# Amplifier_Breakout.net
KiCad netlist of a schematic drawn in EAGLE
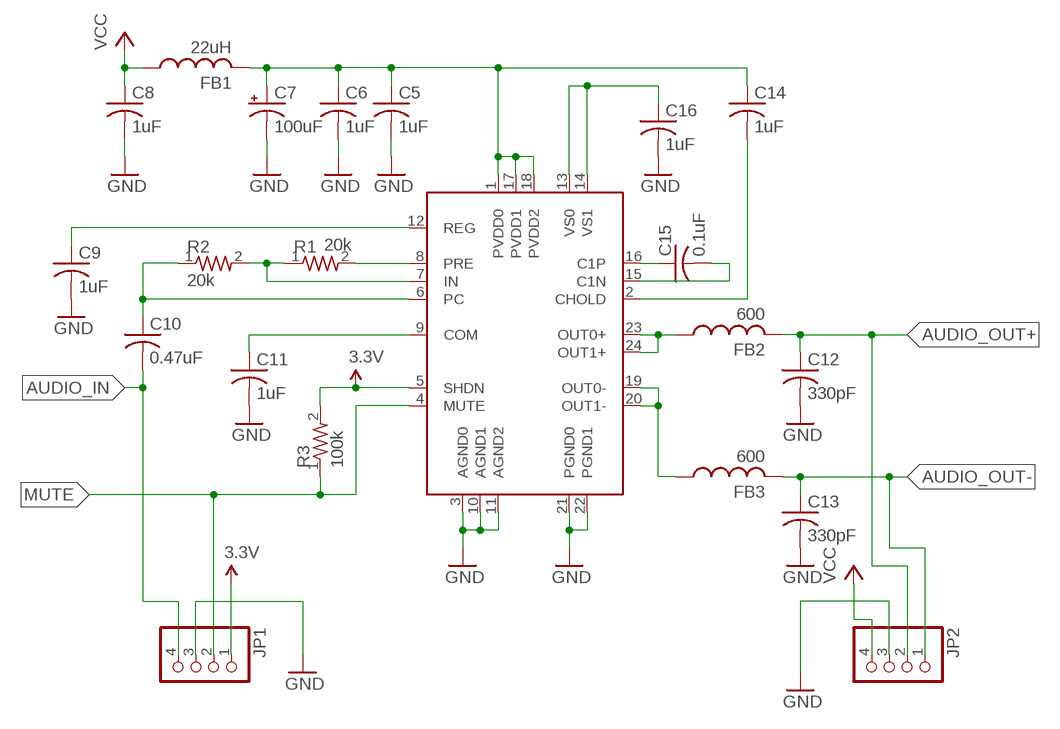
[diagram p0: schematic, sheet 1]

(export (version "E")
  (design (tool "Eeschema 10.0.6"))
  (components
    (comp (ref "C5")
      (value "1uF")
      (footprint "eagle-import:FB-0805")
      (libsource (lib "eagle-import") (part "0805_CAP"))
    )
    (comp (ref "C6")
      (value "1uF")
      (footprint "eagle-import:FB-0805")
      (libsource (lib "eagle-import") (part "0805_CAP"))
    )
    (comp (ref "C7")
      (value "100uF")
      (footprint "eagle-import:CAP_F")
      (libsource (lib "eagle-import") (part "CAP_POL_F"))
    )
    (comp (ref "C8")
      (value "1uF")
      (footprint "eagle-import:FB-0805")
      (libsource (lib "eagle-import") (part "0805_CAP"))
    )
    (comp (ref "C9")
      (value "1uF")
      (footprint "eagle-import:0603_RESISTOR")
      (libsource (lib "eagle-import") (part "0603_CAP"))
    )
    (comp (ref "C10")
      (value "0.47uF")
      (footprint "eagle-import:0603_RESISTOR")
      (libsource (lib "eagle-import") (part "0603_CAP"))
    )
    (comp (ref "C11")
      (value "1uF")
      (footprint "eagle-import:0603_RESISTOR")
      (libsource (lib "eagle-import") (part "0603_CAP"))
    )
    (comp (ref "C12")
      (value "330pF")
      (footprint "eagle-import:0603_RESISTOR")
      (libsource (lib "eagle-import") (part "0603_CAP"))
    )
    (comp (ref "C13")
      (value "330pF")
      (footprint "eagle-import:0603_RESISTOR")
      (libsource (lib "eagle-import") (part "0603_CAP"))
    )
    (comp (ref "C14")
      (value "1uF")
      (footprint "eagle-import:FB-0805")
      (libsource (lib "eagle-import") (part "0805_CAP"))
    )
    (comp (ref "C15")
      (value "0.1uF")
      (footprint "eagle-import:0603_RESISTOR")
      (libsource (lib "eagle-import") (part "0603_CAP"))
    )
    (comp (ref "C16")
      (value "1uF")
      (footprint "eagle-import:0603_RESISTOR")
      (libsource (lib "eagle-import") (part "0603_CAP"))
    )
    (comp (ref "FB1")
      (value "22uH")
      (footprint "eagle-import:FB-0805")
      (libsource (lib "eagle-import") (part "FB"))
    )
    (comp (ref "FB2")
      (value "600")
      (footprint "eagle-import:FB-0805")
      (libsource (lib "eagle-import") (part "FB"))
    )
    (comp (ref "FB3")
      (value "600")
      (footprint "eagle-import:FB-0805")
      (libsource (lib "eagle-import") (part "FB"))
    )
    (comp (ref "JP1")
      (value "PINHD-1X4")
      (footprint "eagle-import:1X04")
      (libsource (lib "eagle-import") (part "PINHD-1X4"))
    )
    (comp (ref "JP2")
      (value "PINHD-1X4")
      (footprint "eagle-import:1X04")
      (libsource (lib "eagle-import") (part "PINHD-1X4"))
    )
    (comp (ref "MAX1")
      (value "MAX9737")
      (footprint "eagle-import:TQFN24")
      (libsource (lib "eagle-import") (part "MAX9737"))
    )
    (comp (ref "R1")
      (value "20k")
      (footprint "eagle-import:0603_RESISTOR")
      (libsource (lib "eagle-import") (part "0603_RESISTOR"))
    )
    (comp (ref "R2")
      (value "20k")
      (footprint "eagle-import:0603_RESISTOR")
      (libsource (lib "eagle-import") (part "0603_RESISTOR"))
    )
    (comp (ref "R3")
      (value "100k")
      (footprint "eagle-import:0603_RESISTOR")
      (libsource (lib "eagle-import") (part "0603_RESISTOR"))
    )
  )
  (nets
    (net (code "1") (name "3.3V") (class "Default")
      (node (ref "JP1") (pin "1") (pinfunction "1_1") (pintype "passive"))
      (node (ref "MAX1") (pin "5") (pinfunction "SHDN_5") (pintype "input"))
      (node (ref "R3") (pin "2") (pinfunction "2_2") (pintype "passive"))
    )
    (net (code "2") (name "AUDIO_IN") (class "Default")
      (node (ref "C10") (pin "2") (pinfunction "2_2") (pintype "passive"))
      (node (ref "JP1") (pin "4") (pinfunction "4_4") (pintype "passive"))
    )
    (net (code "3") (name "AUDIO_OUT+") (class "Default")
      (node (ref "C12") (pin "1") (pinfunction "1_1") (pintype "passive"))
      (node (ref "FB2") (pin "2") (pinfunction "2_2") (pintype "passive"))
      (node (ref "JP2") (pin "2") (pinfunction "2_2") (pintype "passive"))
    )
    (net (code "4") (name "AUDIO_OUT-") (class "Default")
      (node (ref "C13") (pin "1") (pinfunction "1_1") (pintype "passive"))
      (node (ref "FB3") (pin "2") (pinfunction "2_2") (pintype "passive"))
      (node (ref "JP2") (pin "1") (pinfunction "1_1") (pintype "passive"))
    )
    (net (code "5") (name "GND") (class "Default")
      (node (ref "C11") (pin "2") (pinfunction "2_2") (pintype "passive"))
      (node (ref "C12") (pin "2") (pinfunction "2_2") (pintype "passive"))
      (node (ref "C13") (pin "2") (pinfunction "2_2") (pintype "passive"))
      (node (ref "C16") (pin "2") (pinfunction "2_2") (pintype "passive"))
      (node (ref "C5") (pin "2") (pinfunction "2_2") (pintype "passive"))
      (node (ref "C6") (pin "2") (pinfunction "2_2") (pintype "passive"))
      (node (ref "C7") (pin "-") (pinfunction "-_-") (pintype "passive"))
      (node (ref "C8") (pin "2") (pinfunction "2_2") (pintype "passive"))
      (node (ref "C9") (pin "2") (pinfunction "2_2") (pintype "passive"))
      (node (ref "JP1") (pin "3") (pinfunction "3_3") (pintype "passive"))
      (node (ref "JP2") (pin "3") (pinfunction "3_3") (pintype "passive"))
      (node (ref "MAX1") (pin "10") (pinfunction "AGND1_10") (pintype "power_in"))
      (node (ref "MAX1") (pin "11") (pinfunction "AGND2_11") (pintype "power_in"))
      (node (ref "MAX1") (pin "21") (pinfunction "PGND0_21") (pintype "power_in"))
      (node (ref "MAX1") (pin "22") (pinfunction "PGND1_22") (pintype "power_in"))
      (node (ref "MAX1") (pin "3") (pinfunction "AGND0_3") (pintype "power_in"))
    )
    (net (code "6") (name "MUTE") (class "Default")
      (node (ref "JP1") (pin "2") (pinfunction "2_2") (pintype "passive"))
      (node (ref "MAX1") (pin "4") (pinfunction "MUTE_4") (pintype "input"))
      (node (ref "R3") (pin "1") (pinfunction "1_1") (pintype "passive"))
    )
    (net (code "7") (name "Net-(MAX1-C1N)") (class "Default")
      (node (ref "C15") (pin "2") (pinfunction "2_2") (pintype "passive"))
      (node (ref "MAX1") (pin "15") (pinfunction "C1N_15") (pintype "output"))
    )
    (net (code "8") (name "Net-(MAX1-C1P)") (class "Default")
      (node (ref "C15") (pin "1") (pinfunction "1_1") (pintype "passive"))
      (node (ref "MAX1") (pin "16") (pinfunction "C1P_16") (pintype "output"))
    )
    (net (code "9") (name "Net-(MAX1-CHOLD)") (class "Default")
      (node (ref "C14") (pin "2") (pinfunction "2_2") (pintype "passive"))
      (node (ref "MAX1") (pin "2") (pinfunction "CHOLD_2") (pintype "output"))
    )
    (net (code "10") (name "Net-(MAX1-COM)") (class "Default")
      (node (ref "C11") (pin "1") (pinfunction "1_1") (pintype "passive"))
      (node (ref "MAX1") (pin "9") (pinfunction "COM_9") (pintype "input"))
    )
    (net (code "11") (name "Net-(MAX1-IN)") (class "Default")
      (node (ref "MAX1") (pin "7") (pinfunction "IN_7") (pintype "input"))
      (node (ref "R1") (pin "1") (pinfunction "1_1") (pintype "passive"))
      (node (ref "R2") (pin "2") (pinfunction "2_2") (pintype "passive"))
    )
    (net (code "12") (name "Net-(MAX1-OUT0+)") (class "Default")
      (node (ref "FB2") (pin "1") (pinfunction "1_1") (pintype "passive"))
      (node (ref "MAX1") (pin "23") (pinfunction "OUT0+_23") (pintype "output"))
      (node (ref "MAX1") (pin "24") (pinfunction "OUT1+_24") (pintype "output"))
    )
    (net (code "13") (name "Net-(MAX1-OUT0-)") (class "Default")
      (node (ref "FB3") (pin "1") (pinfunction "1_1") (pintype "passive"))
      (node (ref "MAX1") (pin "19") (pinfunction "OUT0-_19") (pintype "output"))
      (node (ref "MAX1") (pin "20") (pinfunction "OUT1-_20") (pintype "output"))
    )
    (net (code "14") (name "Net-(MAX1-PC)") (class "Default")
      (node (ref "C10") (pin "1") (pinfunction "1_1") (pintype "passive"))
      (node (ref "MAX1") (pin "6") (pinfunction "PC_6") (pintype "input"))
      (node (ref "R2") (pin "1") (pinfunction "1_1") (pintype "passive"))
    )
    (net (code "15") (name "Net-(MAX1-PRE)") (class "Default")
      (node (ref "MAX1") (pin "8") (pinfunction "PRE_8") (pintype "output"))
      (node (ref "R1") (pin "2") (pinfunction "2_2") (pintype "passive"))
    )
    (net (code "16") (name "Net-(MAX1-PVDD0)") (class "Default")
      (node (ref "C14") (pin "1") (pinfunction "1_1") (pintype "passive"))
      (node (ref "C5") (pin "1") (pinfunction "1_1") (pintype "passive"))
      (node (ref "C6") (pin "1") (pinfunction "1_1") (pintype "passive"))
      (node (ref "C7") (pin "+") (pinfunction "+_+") (pintype "passive"))
      (node (ref "FB1") (pin "2") (pinfunction "2_2") (pintype "passive"))
      (node (ref "MAX1") (pin "1") (pinfunction "PVDD0_1") (pintype "power_in"))
      (node (ref "MAX1") (pin "17") (pinfunction "PVDD1_17") (pintype "power_in"))
      (node (ref "MAX1") (pin "18") (pinfunction "PVDD2_18") (pintype "power_in"))
    )
    (net (code "17") (name "Net-(MAX1-REG)") (class "Default")
      (node (ref "C9") (pin "1") (pinfunction "1_1") (pintype "passive"))
      (node (ref "MAX1") (pin "12") (pinfunction "REG_12") (pintype "output"))
    )
    (net (code "18") (name "Net-(MAX1-VS0)") (class "Default")
      (node (ref "C16") (pin "1") (pinfunction "1_1") (pintype "passive"))
      (node (ref "MAX1") (pin "13") (pinfunction "VS0_13") (pintype "output"))
      (node (ref "MAX1") (pin "14") (pinfunction "VS1_14") (pintype "output"))
    )
    (net (code "19") (name "VCC") (class "Default")
      (node (ref "C8") (pin "1") (pinfunction "1_1") (pintype "passive"))
      (node (ref "FB1") (pin "1") (pinfunction "1_1") (pintype "passive"))
      (node (ref "JP2") (pin "4") (pinfunction "4_4") (pintype "passive"))
    )
  )
)
